# tconnectors.net
KiCad netlist of a schematic drawn in EAGLE
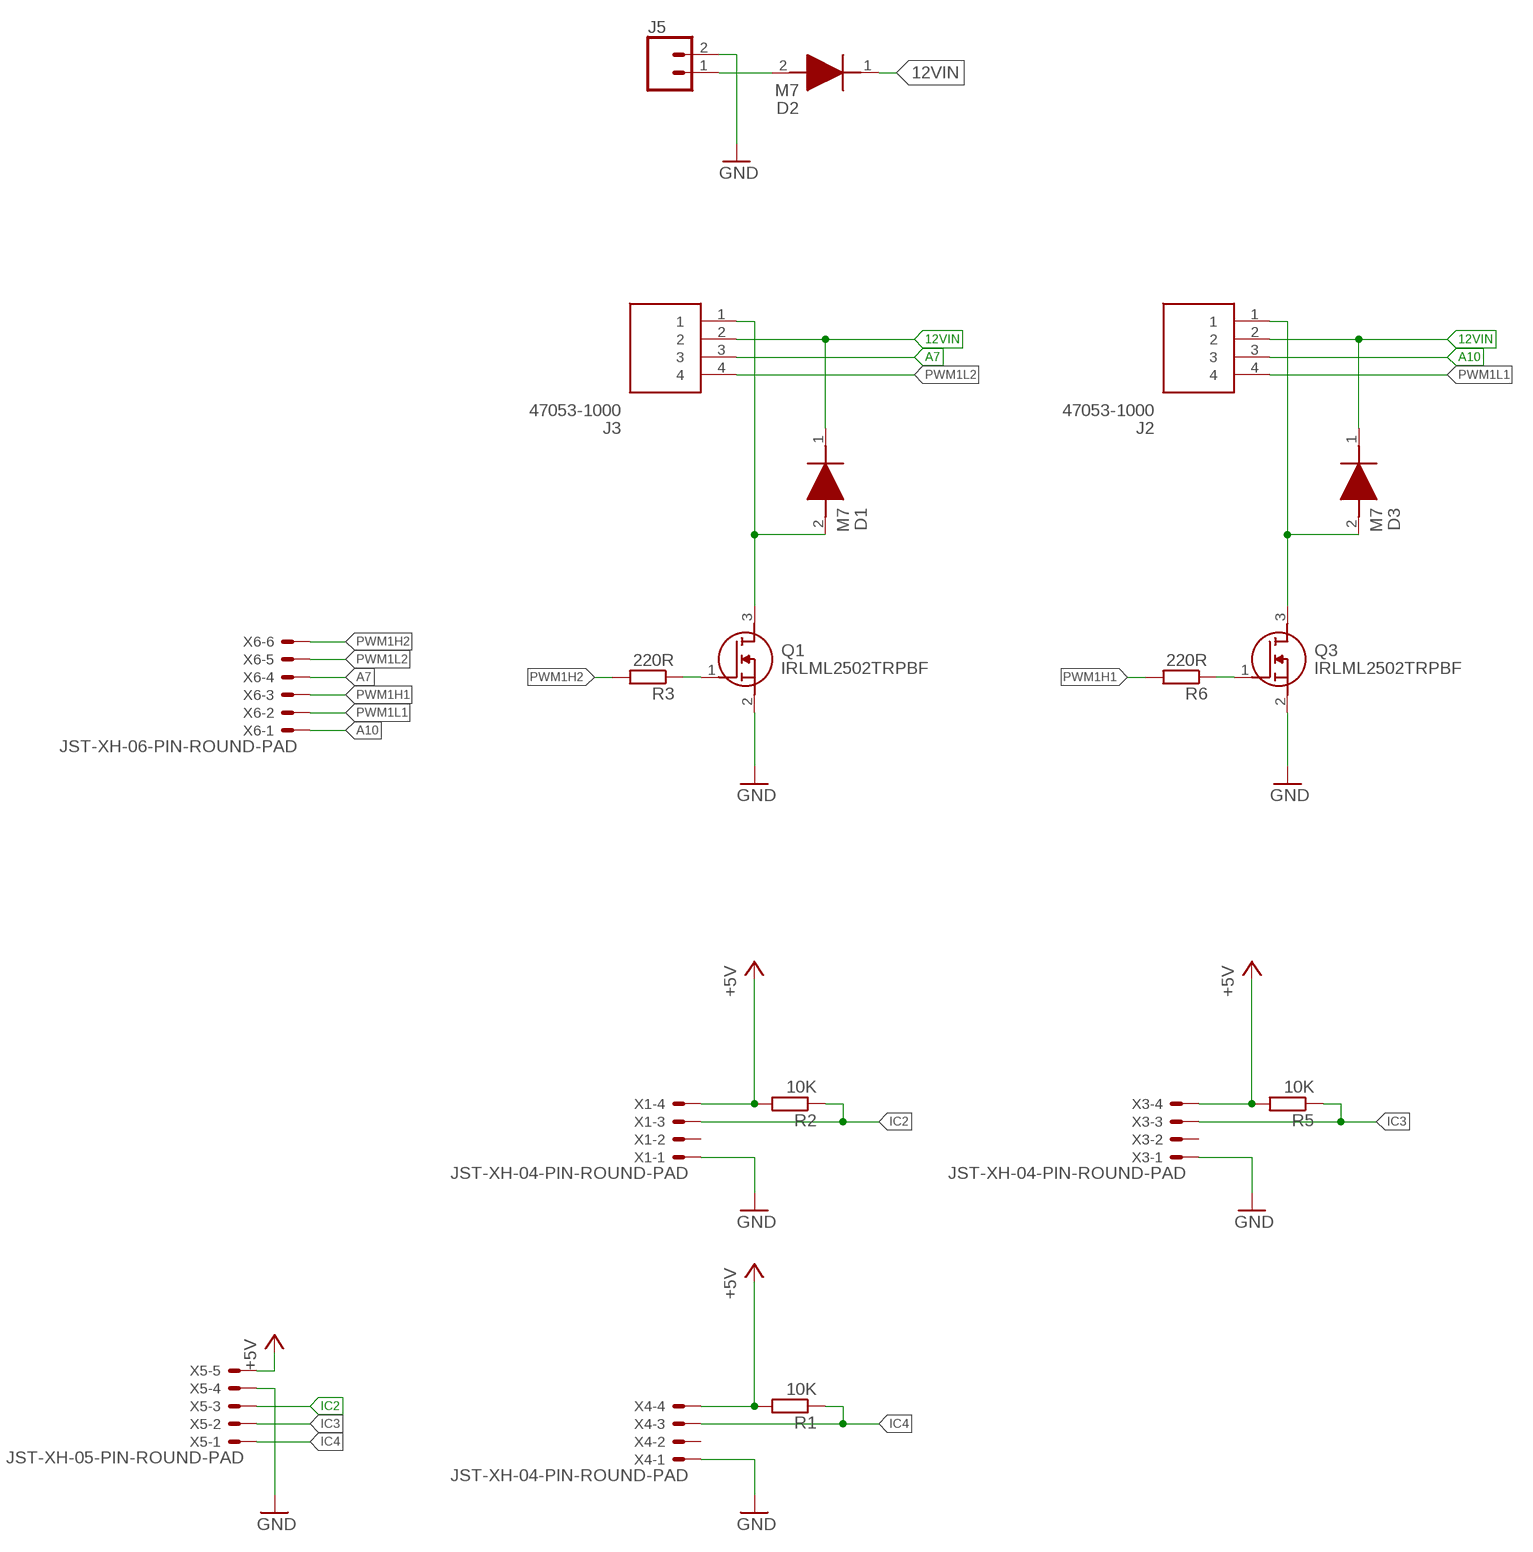
[diagram p0: schematic, sheet 1]

(export (version "E")
  (design (tool "Eeschema 10.0.6"))
  (components
    (comp (ref "D1")
      (value "M7")
      (footprint "eagle-import:DIOM5327X240N")
      (fields (field (name "MOUSER_PART_NUMBER") "637-M7"))
      (libsource (lib "eagle-import") (part "M7"))
    )
    (comp (ref "D2")
      (value "M7")
      (footprint "eagle-import:DIOM5327X240N")
      (fields (field (name "MOUSER_PART_NUMBER") "637-M7"))
      (libsource (lib "eagle-import") (part "M7"))
    )
    (comp (ref "D3")
      (value "M7")
      (footprint "eagle-import:DIOM5327X240N")
      (fields (field (name "MOUSER_PART_NUMBER") "637-M7"))
      (libsource (lib "eagle-import") (part "M7"))
    )
    (comp (ref "J2")
      (value "47053-1000")
      (footprint "eagle-import:470531000")
      (fields (field (name "MOUSER_PART_NUMBER") "538-47053-1000"))
      (libsource (lib "eagle-import") (part "47053-1000"))
    )
    (comp (ref "J3")
      (value "47053-1000")
      (footprint "eagle-import:470531000")
      (fields (field (name "MOUSER_PART_NUMBER") "538-47053-1000"))
      (libsource (lib "eagle-import") (part "47053-1000"))
    )
    (comp (ref "J5")
      (value "CONN_025MM")
      (footprint "eagle-import:SCREWTERMINAL-5MM-2")
      (libsource (lib "eagle-import") (part "CONN_025MM"))
    )
    (comp (ref "Q1")
      (value "IRLML2502TRPBF")
      (footprint "eagle-import:SOT95P237X112-3N")
      (fields (field (name "MOUSER_PART_NUMBER") "942-IRLML2502TRPBF"))
      (libsource (lib "eagle-import") (part "IRLML2502TRPBF"))
    )
    (comp (ref "Q3")
      (value "IRLML2502TRPBF")
      (footprint "eagle-import:SOT95P237X112-3N")
      (fields (field (name "MOUSER_PART_NUMBER") "942-IRLML2502TRPBF"))
      (libsource (lib "eagle-import") (part "IRLML2502TRPBF"))
    )
    (comp (ref "R1")
      (value "10K")
      (footprint "eagle-import:R0805")
      (libsource (lib "eagle-import") (part "R-EU_R0805"))
    )
    (comp (ref "R2")
      (value "10K")
      (footprint "eagle-import:R0805")
      (libsource (lib "eagle-import") (part "R-EU_R0805"))
    )
    (comp (ref "R3")
      (value "220R")
      (footprint "eagle-import:R0805")
      (libsource (lib "eagle-import") (part "R-EU_R0805"))
    )
    (comp (ref "R5")
      (value "10K")
      (footprint "eagle-import:R0805")
      (libsource (lib "eagle-import") (part "R-EU_R0805"))
    )
    (comp (ref "R6")
      (value "220R")
      (footprint "eagle-import:R0805")
      (libsource (lib "eagle-import") (part "R-EU_R0805"))
    )
    (comp (ref "X1")
      (value "JST-XH-04-PIN-ROUND-PAD")
      (footprint "eagle-import:JST-XH-04-PACKAGE-ROUND-PAD")
      (libsource (lib "eagle-import") (part "JST-XH-04-PIN-ROUND-PAD"))
    )
    (comp (ref "X3")
      (value "JST-XH-04-PIN-ROUND-PAD")
      (footprint "eagle-import:JST-XH-04-PACKAGE-ROUND-PAD")
      (libsource (lib "eagle-import") (part "JST-XH-04-PIN-ROUND-PAD"))
    )
    (comp (ref "X4")
      (value "JST-XH-04-PIN-ROUND-PAD")
      (footprint "eagle-import:JST-XH-04-PACKAGE-ROUND-PAD")
      (libsource (lib "eagle-import") (part "JST-XH-04-PIN-ROUND-PAD"))
    )
    (comp (ref "X5")
      (value "JST-XH-05-PIN-ROUND-PAD")
      (footprint "eagle-import:JST-XH-05-PACKAGE-ROUND-PAD")
      (libsource (lib "eagle-import") (part "JST-XH-05-PIN-ROUND-PAD"))
    )
    (comp (ref "X6")
      (value "JST-XH-06-PIN-ROUND-PAD")
      (footprint "eagle-import:JST-XH-06-PACKAGE-ROUND-PAD")
      (libsource (lib "eagle-import") (part "JST-XH-06-PIN-ROUND-PAD"))
    )
  )
  (nets
    (net (code "1") (name "+5V") (class "Default")
      (node (ref "R1") (pin "2") (pinfunction "2_2") (pintype "passive"))
      (node (ref "R2") (pin "2") (pinfunction "2_2") (pintype "passive"))
      (node (ref "R5") (pin "2") (pinfunction "2_2") (pintype "passive"))
      (node (ref "X1") (pin "4") (pinfunction "S_4") (pintype "passive"))
      (node (ref "X3") (pin "4") (pinfunction "S_4") (pintype "passive"))
      (node (ref "X4") (pin "4") (pinfunction "S_4") (pintype "passive"))
      (node (ref "X5") (pin "5") (pinfunction "S_5") (pintype "passive"))
    )
    (net (code "2") (name "12VIN") (class "Default")
      (node (ref "D1") (pin "1") (pinfunction "K_1") (pintype "bidirectional"))
      (node (ref "D2") (pin "1") (pinfunction "K_1") (pintype "bidirectional"))
      (node (ref "D3") (pin "1") (pinfunction "K_1") (pintype "bidirectional"))
      (node (ref "J2") (pin "2") (pinfunction "2_2") (pintype "bidirectional"))
      (node (ref "J3") (pin "2") (pinfunction "2_2") (pintype "bidirectional"))
    )
    (net (code "3") (name "A7") (class "Default")
      (node (ref "J3") (pin "3") (pinfunction "3_3") (pintype "bidirectional"))
      (node (ref "X6") (pin "4") (pinfunction "S_4") (pintype "passive"))
    )
    (net (code "4") (name "A10") (class "Default")
      (node (ref "J2") (pin "3") (pinfunction "3_3") (pintype "bidirectional"))
      (node (ref "X6") (pin "1") (pinfunction "S_1") (pintype "passive"))
    )
    (net (code "5") (name "GND") (class "Default")
      (node (ref "J5") (pin "2") (pinfunction "2_2") (pintype "passive"))
      (node (ref "Q1") (pin "2") (pinfunction "S_2") (pintype "bidirectional"))
      (node (ref "Q3") (pin "2") (pinfunction "S_2") (pintype "bidirectional"))
      (node (ref "X1") (pin "1") (pinfunction "S_1") (pintype "passive"))
      (node (ref "X3") (pin "1") (pinfunction "S_1") (pintype "passive"))
      (node (ref "X4") (pin "1") (pinfunction "S_1") (pintype "passive"))
      (node (ref "X5") (pin "4") (pinfunction "S_4") (pintype "passive"))
    )
    (net (code "6") (name "IC2") (class "Default")
      (node (ref "R2") (pin "1") (pinfunction "1_1") (pintype "passive"))
      (node (ref "X1") (pin "3") (pinfunction "S_3") (pintype "passive"))
      (node (ref "X5") (pin "3") (pinfunction "S_3") (pintype "passive"))
    )
    (net (code "7") (name "IC3") (class "Default")
      (node (ref "R5") (pin "1") (pinfunction "1_1") (pintype "passive"))
      (node (ref "X3") (pin "3") (pinfunction "S_3") (pintype "passive"))
      (node (ref "X5") (pin "2") (pinfunction "S_2") (pintype "passive"))
    )
    (net (code "8") (name "IC4") (class "Default")
      (node (ref "R1") (pin "1") (pinfunction "1_1") (pintype "passive"))
      (node (ref "X4") (pin "3") (pinfunction "S_3") (pintype "passive"))
      (node (ref "X5") (pin "1") (pinfunction "S_1") (pintype "passive"))
    )
    (net (code "9") (name "Net-(D1-A)") (class "Default")
      (node (ref "D1") (pin "2") (pinfunction "A_2") (pintype "bidirectional"))
      (node (ref "J3") (pin "1") (pinfunction "1_1") (pintype "bidirectional"))
      (node (ref "Q1") (pin "3") (pinfunction "D_3") (pintype "bidirectional"))
    )
    (net (code "10") (name "Net-(D2-A)") (class "Default")
      (node (ref "D2") (pin "2") (pinfunction "A_2") (pintype "bidirectional"))
      (node (ref "J5") (pin "1") (pinfunction "1_1") (pintype "passive"))
    )
    (net (code "11") (name "Net-(D3-A)") (class "Default")
      (node (ref "D3") (pin "2") (pinfunction "A_2") (pintype "bidirectional"))
      (node (ref "J2") (pin "1") (pinfunction "1_1") (pintype "bidirectional"))
      (node (ref "Q3") (pin "3") (pinfunction "D_3") (pintype "bidirectional"))
    )
    (net (code "12") (name "Net-(Q1-G)") (class "Default")
      (node (ref "Q1") (pin "1") (pinfunction "G_1") (pintype "bidirectional"))
      (node (ref "R3") (pin "1") (pinfunction "1_1") (pintype "passive"))
    )
    (net (code "13") (name "Net-(Q3-G)") (class "Default")
      (node (ref "Q3") (pin "1") (pinfunction "G_1") (pintype "bidirectional"))
      (node (ref "R6") (pin "1") (pinfunction "1_1") (pintype "passive"))
    )
    (net (code "14") (name "PWM1H1") (class "Default")
      (node (ref "R6") (pin "2") (pinfunction "2_2") (pintype "passive"))
      (node (ref "X6") (pin "3") (pinfunction "S_3") (pintype "passive"))
    )
    (net (code "15") (name "PWM1H2") (class "Default")
      (node (ref "R3") (pin "2") (pinfunction "2_2") (pintype "passive"))
      (node (ref "X6") (pin "6") (pinfunction "S_6") (pintype "passive"))
    )
    (net (code "16") (name "PWM1L1") (class "Default")
      (node (ref "J2") (pin "4") (pinfunction "4_4") (pintype "bidirectional"))
      (node (ref "X6") (pin "2") (pinfunction "S_2") (pintype "passive"))
    )
    (net (code "17") (name "PWM1L2") (class "Default")
      (node (ref "J3") (pin "4") (pinfunction "4_4") (pintype "bidirectional"))
      (node (ref "X6") (pin "5") (pinfunction "S_5") (pintype "passive"))
    )
    (net (code "18") (name "unconnected-(X1B-S-Pad2)") (class "Default")
      (node (ref "X1") (pin "2") (pinfunction "S_2") (pintype "passive"))
    )
    (net (code "19") (name "unconnected-(X3B-S-Pad2)") (class "Default")
      (node (ref "X3") (pin "2") (pinfunction "S_2") (pintype "passive"))
    )
    (net (code "20") (name "unconnected-(X4B-S-Pad2)") (class "Default")
      (node (ref "X4") (pin "2") (pinfunction "S_2") (pintype "passive"))
    )
  )
)
